# 05_-_CONNECTOR.net
KiCad netlist of a schematic drawn in Altium Designer
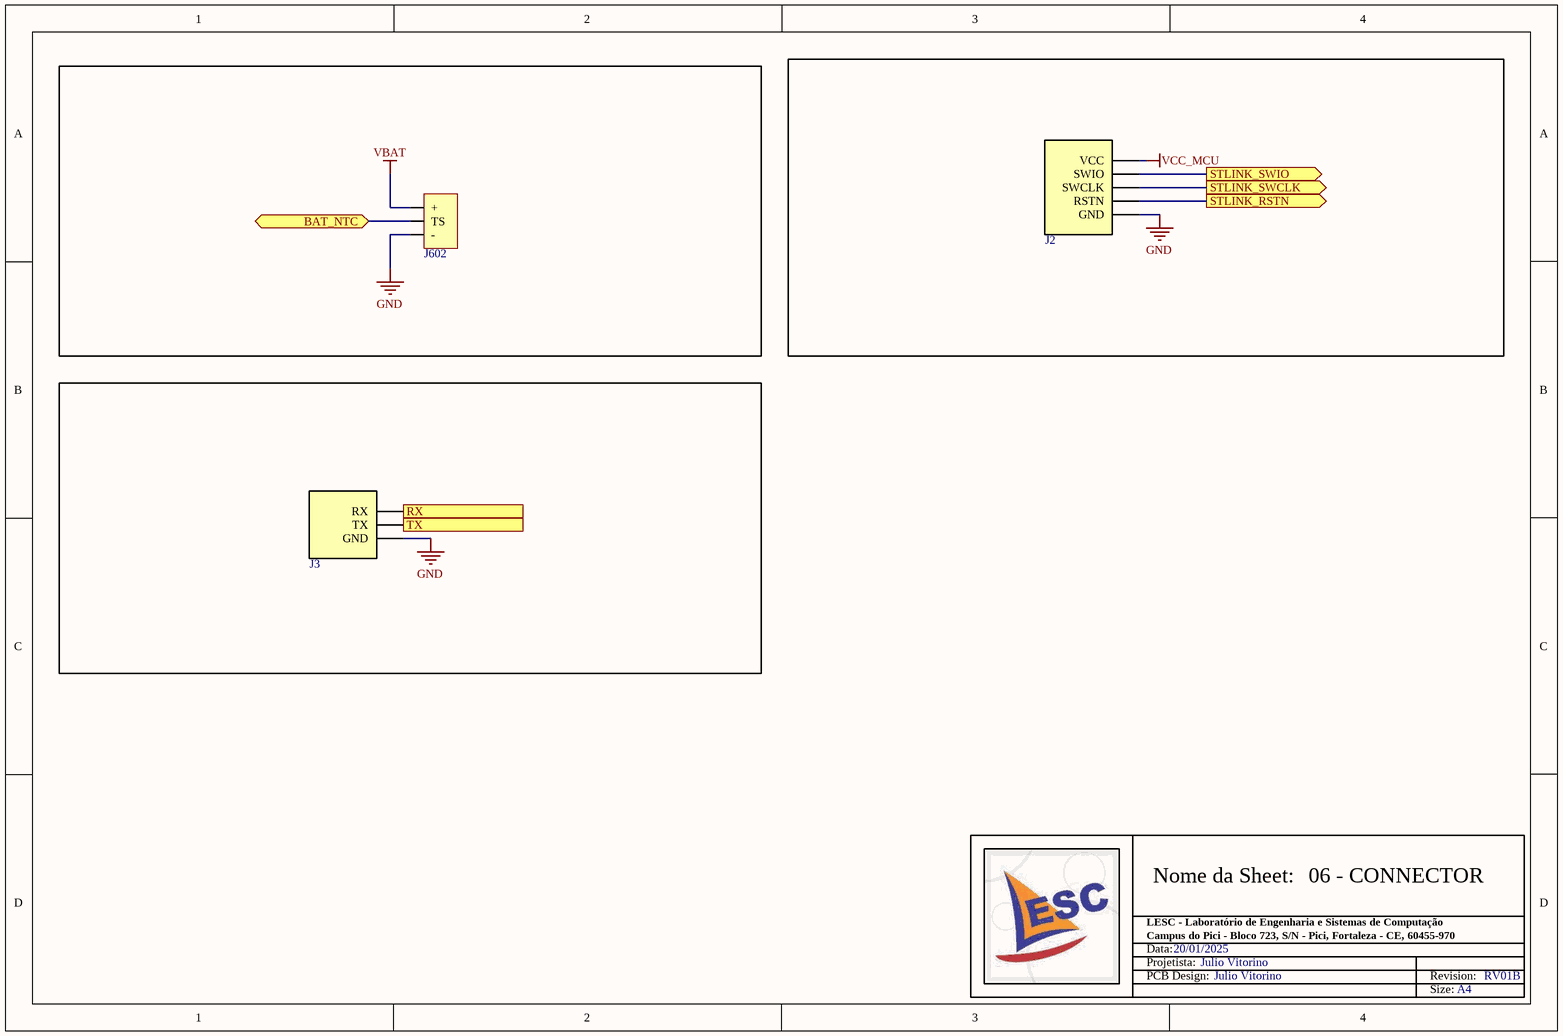
[diagram p0: 05 - CONNECTOR.SchDoc]

(export (version "E")
  (design (tool "Eeschema 10.0.6"))
  (components
    (comp (ref "J2")
      (value "CONN PCB 5PIN")
      (footprint "SWD CONNECTOR")
      (libsource (lib "Schlib1") (part "CONN PCB 5PIN"))
    )
    (comp (ref "J3")
      (value "CONN PCB 3PIN")
      (footprint "DEBUG CONNECTOR")
      (libsource (lib "Schlib1") (part "CONN PCB 3PIN"))
    )
    (comp (ref "J602")
      (value "10114830-11103LF")
      (footprint "CONNECTOR BATTERY")
      (description "CONN HEADER SMD R/A 3POS 1.25MM")
      (fields
        (field (name "MANUFACTURER") "Amphenol ICC")
        (field (name "EVENDOR PART#") "609-10114830-11103LFCT-ND")
      )
      (libsource (lib "Schlib1") (part "CONN HEADER SMD R/A 3POS 1.25MM"))
    )
  )
  (nets
    (net (code "1") (name "/BAT_NTC") (class "Default")
      (node (ref "J602") (pin "2") (pinfunction "TS_2") (pintype "passive"))
    )
    (net (code "2") (name "/RX") (class "Default")
      (node (ref "J3") (pin "1") (pinfunction "RX_1") (pintype "passive"))
    )
    (net (code "3") (name "/STLINK_RSTN") (class "Default")
      (node (ref "J2") (pin "4") (pinfunction "RSTN_4") (pintype "passive"))
    )
    (net (code "4") (name "/STLINK_SWCLK") (class "Default")
      (node (ref "J2") (pin "3") (pinfunction "SWCLK_3") (pintype "passive"))
    )
    (net (code "5") (name "/STLINK_SWIO") (class "Default")
      (node (ref "J2") (pin "2") (pinfunction "SWIO_2") (pintype "passive"))
    )
    (net (code "6") (name "/TX") (class "Default")
      (node (ref "J3") (pin "2") (pinfunction "TX_2") (pintype "passive"))
    )
    (net (code "7") (name "GND") (class "Default")
      (node (ref "J2") (pin "5") (pinfunction "GND_5") (pintype "passive"))
      (node (ref "J3") (pin "3") (pinfunction "GND_3") (pintype "passive"))
      (node (ref "J602") (pin "1") (pinfunction "-_1") (pintype "passive"))
    )
    (net (code "8") (name "VBAT") (class "Default")
      (node (ref "J602") (pin "3") (pinfunction "+_3") (pintype "passive"))
    )
    (net (code "9") (name "VCC_MCU") (class "Default")
      (node (ref "J2") (pin "1") (pinfunction "VCC_1") (pintype "passive"))
    )
  )
)
